# bootloader.net
KiCad netlist of a schematic drawn in EAGLE
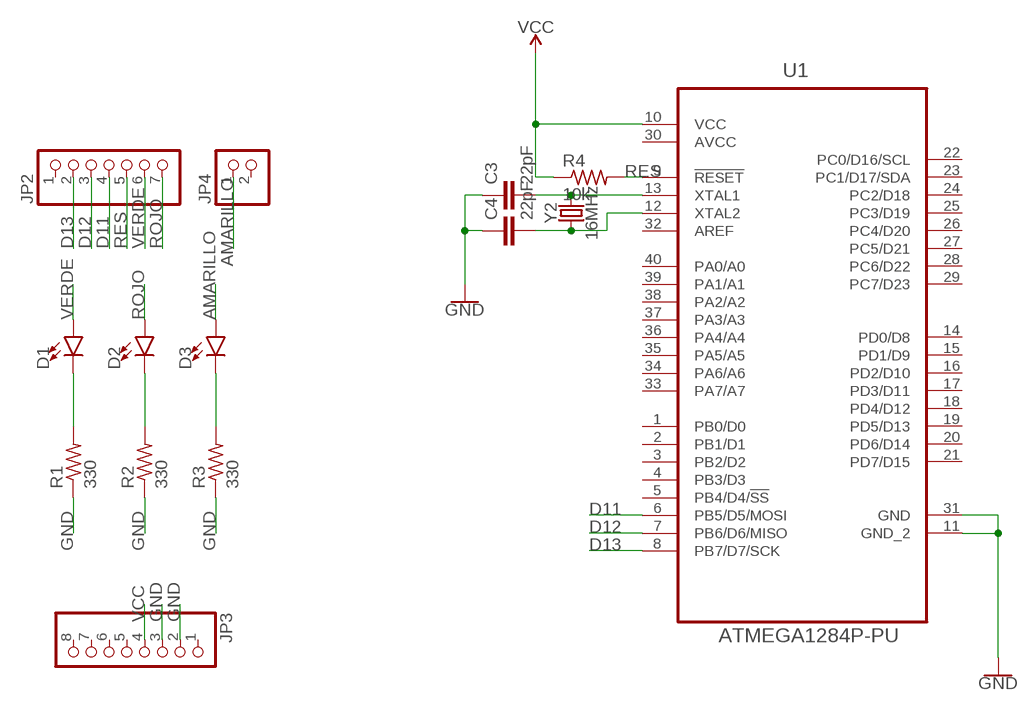
[diagram p0: schematic, sheet 1]

(export (version "E")
  (design (tool "Eeschema 10.0.6"))
  (components
    (comp (ref "C3")
      (value "22pF")
      (footprint "eagle-import:C1206")
      (libsource (lib "eagle-import") (part "C-EUC1206"))
    )
    (comp (ref "C4")
      (value "22pF")
      (footprint "eagle-import:C1206")
      (libsource (lib "eagle-import") (part "C-EUC1206"))
    )
    (comp (ref "D1")
      (value "LED1206")
      (footprint "eagle-import:LED-1206")
      (libsource (lib "eagle-import") (part "LED1206"))
    )
    (comp (ref "D2")
      (value "LED1206")
      (footprint "eagle-import:LED-1206")
      (libsource (lib "eagle-import") (part "LED1206"))
    )
    (comp (ref "D3")
      (value "LED1206")
      (footprint "eagle-import:LED-1206")
      (libsource (lib "eagle-import") (part "LED1206"))
    )
    (comp (ref "JP2")
      (value "PINHD-1X7")
      (footprint "eagle-import:1X07")
      (libsource (lib "eagle-import") (part "PINHD-1X7"))
    )
    (comp (ref "JP3")
      (value "PINHD-1X8")
      (footprint "eagle-import:1X08")
      (libsource (lib "eagle-import") (part "PINHD-1X8"))
    )
    (comp (ref "JP4")
      (value "PINHD-1X2")
      (footprint "eagle-import:1X02")
      (libsource (lib "eagle-import") (part "PINHD-1X2"))
    )
    (comp (ref "R1")
      (value "330")
      (footprint "eagle-import:R1206")
      (libsource (lib "eagle-import") (part "R-US_R1206"))
    )
    (comp (ref "R2")
      (value "330")
      (footprint "eagle-import:R1206")
      (libsource (lib "eagle-import") (part "R-US_R1206"))
    )
    (comp (ref "R3")
      (value "330")
      (footprint "eagle-import:R1206")
      (libsource (lib "eagle-import") (part "R-US_R1206"))
    )
    (comp (ref "R4")
      (value "10k")
      (footprint "eagle-import:R1206")
      (libsource (lib "eagle-import") (part "rcl_R-US_R1206"))
    )
    (comp (ref "U1")
      (value "ATMEGA1284P-PU")
      (footprint "eagle-import:DIP254P1524X483-40")
      (fields (field (name "MF") "Microchip"))
      (libsource (lib "eagle-import") (part "ATMEGA1284P-PU"))
    )
    (comp (ref "Y2")
      (value "16MHz")
      (footprint "eagle-import:CRYSTAL-SMD-5X3.2-4PAD")
      (libsource (lib "eagle-import") (part "CRYSTALSMD-5X3.2-4PAD"))
    )
  )
  (nets
    (net (code "1") (name "/AMARILLO") (class "Default")
      (node (ref "D3") (pin "A") (pinfunction "A_A") (pintype "passive"))
      (node (ref "JP4") (pin "1") (pinfunction "1_1") (pintype "passive"))
    )
    (net (code "2") (name "/AVCC") (class "Default")
      (node (ref "U1") (pin "30") (pinfunction "AVCC_30") (pintype "power_in"))
    )
    (net (code "3") (name "/D11") (class "Default")
      (node (ref "JP2") (pin "4") (pinfunction "4_4") (pintype "passive"))
      (node (ref "U1") (pin "6") (pinfunction "PB5/D5/MOSI_6") (pintype "bidirectional"))
    )
    (net (code "4") (name "/D12") (class "Default")
      (node (ref "JP2") (pin "3") (pinfunction "3_3") (pintype "passive"))
      (node (ref "U1") (pin "7") (pinfunction "PB6/D6/MISO_7") (pintype "bidirectional"))
    )
    (net (code "5") (name "/D13") (class "Default")
      (node (ref "JP2") (pin "2") (pinfunction "2_2") (pintype "passive"))
      (node (ref "U1") (pin "8") (pinfunction "PB7/D7/SCK_8") (pintype "bidirectional"))
    )
    (net (code "6") (name "/RES") (class "Default")
      (node (ref "JP2") (pin "5") (pinfunction "5_5") (pintype "passive"))
      (node (ref "R4") (pin "2") (pinfunction "2_2") (pintype "passive"))
      (node (ref "U1") (pin "9") (pinfunction "~{RESET}_9") (pintype "input"))
    )
    (net (code "7") (name "/ROJO") (class "Default")
      (node (ref "D2") (pin "A") (pinfunction "A_A") (pintype "passive"))
      (node (ref "JP2") (pin "7") (pinfunction "7_7") (pintype "passive"))
    )
    (net (code "8") (name "/VERDE") (class "Default")
      (node (ref "D1") (pin "A") (pinfunction "A_A") (pintype "passive"))
      (node (ref "JP2") (pin "6") (pinfunction "6_6") (pintype "passive"))
    )
    (net (code "9") (name "GND") (class "Default")
      (node (ref "C3") (pin "1") (pinfunction "1_1") (pintype "passive"))
      (node (ref "C4") (pin "1") (pinfunction "1_1") (pintype "passive"))
      (node (ref "JP3") (pin "2") (pinfunction "2_2") (pintype "passive"))
      (node (ref "JP3") (pin "3") (pinfunction "3_3") (pintype "passive"))
      (node (ref "R1") (pin "1") (pinfunction "1_1") (pintype "passive"))
      (node (ref "R2") (pin "1") (pinfunction "1_1") (pintype "passive"))
      (node (ref "R3") (pin "1") (pinfunction "1_1") (pintype "passive"))
      (node (ref "U1") (pin "11") (pinfunction "GND_2_11") (pintype "passive"))
      (node (ref "U1") (pin "31") (pinfunction "GND_31") (pintype "passive"))
    )
    (net (code "10") (name "Net-(D1-PadC)") (class "Default")
      (node (ref "D1") (pin "C") (pinfunction "C_C") (pintype "passive"))
      (node (ref "R1") (pin "2") (pinfunction "2_2") (pintype "passive"))
    )
    (net (code "11") (name "Net-(D2-PadC)") (class "Default")
      (node (ref "D2") (pin "C") (pinfunction "C_C") (pintype "passive"))
      (node (ref "R2") (pin "2") (pinfunction "2_2") (pintype "passive"))
    )
    (net (code "12") (name "Net-(D3-PadC)") (class "Default")
      (node (ref "D3") (pin "C") (pinfunction "C_C") (pintype "passive"))
      (node (ref "R3") (pin "2") (pinfunction "2_2") (pintype "passive"))
    )
    (net (code "13") (name "Net-(U1-XTAL1)") (class "Default")
      (node (ref "C3") (pin "2") (pinfunction "2_2") (pintype "passive"))
      (node (ref "U1") (pin "13") (pinfunction "XTAL1_13") (pintype "input"))
      (node (ref "Y2") (pin "3") (pinfunction "2_3") (pintype "passive"))
    )
    (net (code "14") (name "Net-(U1-XTAL2)") (class "Default")
      (node (ref "C4") (pin "2") (pinfunction "2_2") (pintype "passive"))
      (node (ref "U1") (pin "12") (pinfunction "XTAL2_12") (pintype "output"))
      (node (ref "Y2") (pin "1") (pinfunction "1_1") (pintype "passive"))
    )
    (net (code "15") (name "VCC") (class "Default")
      (node (ref "JP3") (pin "4") (pinfunction "4_4") (pintype "passive"))
      (node (ref "R4") (pin "1") (pinfunction "1_1") (pintype "passive"))
      (node (ref "U1") (pin "10") (pinfunction "VCC_10") (pintype "power_in"))
    )
    (net (code "16") (name "unconnected-(JP2-Pad1)") (class "Default")
      (node (ref "JP2") (pin "1") (pinfunction "1_1") (pintype "passive"))
    )
    (net (code "17") (name "unconnected-(JP3-Pad1)") (class "Default")
      (node (ref "JP3") (pin "1") (pinfunction "1_1") (pintype "passive"))
    )
    (net (code "18") (name "unconnected-(JP3-Pad5)") (class "Default")
      (node (ref "JP3") (pin "5") (pinfunction "5_5") (pintype "passive"))
    )
    (net (code "19") (name "unconnected-(JP3-Pad6)") (class "Default")
      (node (ref "JP3") (pin "6") (pinfunction "6_6") (pintype "passive"))
    )
    (net (code "20") (name "unconnected-(JP3-Pad7)") (class "Default")
      (node (ref "JP3") (pin "7") (pinfunction "7_7") (pintype "passive"))
    )
    (net (code "21") (name "unconnected-(JP3-Pad8)") (class "Default")
      (node (ref "JP3") (pin "8") (pinfunction "8_8") (pintype "passive"))
    )
    (net (code "22") (name "unconnected-(JP4-Pad2)") (class "Default")
      (node (ref "JP4") (pin "2") (pinfunction "2_2") (pintype "passive"))
    )
    (net (code "23") (name "unconnected-(U1-AREF-Pad32)") (class "Default")
      (node (ref "U1") (pin "32") (pinfunction "AREF_32") (pintype "input"))
    )
    (net (code "24") (name "unconnected-(U1-PA0{slash}A0-Pad40)") (class "Default")
      (node (ref "U1") (pin "40") (pinfunction "PA0/A0_40") (pintype "bidirectional"))
    )
    (net (code "25") (name "unconnected-(U1-PA1{slash}A1-Pad39)") (class "Default")
      (node (ref "U1") (pin "39") (pinfunction "PA1/A1_39") (pintype "bidirectional"))
    )
    (net (code "26") (name "unconnected-(U1-PA2{slash}A2-Pad38)") (class "Default")
      (node (ref "U1") (pin "38") (pinfunction "PA2/A2_38") (pintype "bidirectional"))
    )
    (net (code "27") (name "unconnected-(U1-PA3{slash}A3-Pad37)") (class "Default")
      (node (ref "U1") (pin "37") (pinfunction "PA3/A3_37") (pintype "bidirectional"))
    )
    (net (code "28") (name "unconnected-(U1-PA4{slash}A4-Pad36)") (class "Default")
      (node (ref "U1") (pin "36") (pinfunction "PA4/A4_36") (pintype "bidirectional"))
    )
    (net (code "29") (name "unconnected-(U1-PA5{slash}A5-Pad35)") (class "Default")
      (node (ref "U1") (pin "35") (pinfunction "PA5/A5_35") (pintype "bidirectional"))
    )
    (net (code "30") (name "unconnected-(U1-PA6{slash}A6-Pad34)") (class "Default")
      (node (ref "U1") (pin "34") (pinfunction "PA6/A6_34") (pintype "bidirectional"))
    )
    (net (code "31") (name "unconnected-(U1-PA7{slash}A7-Pad33)") (class "Default")
      (node (ref "U1") (pin "33") (pinfunction "PA7/A7_33") (pintype "bidirectional"))
    )
    (net (code "32") (name "unconnected-(U1-PB0{slash}D0-Pad1)") (class "Default")
      (node (ref "U1") (pin "1") (pinfunction "PB0/D0_1") (pintype "bidirectional"))
    )
    (net (code "33") (name "unconnected-(U1-PB1{slash}D1-Pad2)") (class "Default")
      (node (ref "U1") (pin "2") (pinfunction "PB1/D1_2") (pintype "bidirectional"))
    )
    (net (code "34") (name "unconnected-(U1-PB2{slash}D2-Pad3)") (class "Default")
      (node (ref "U1") (pin "3") (pinfunction "PB2/D2_3") (pintype "bidirectional"))
    )
    (net (code "35") (name "unconnected-(U1-PB3{slash}D3-Pad4)") (class "Default")
      (node (ref "U1") (pin "4") (pinfunction "PB3/D3_4") (pintype "bidirectional"))
    )
    (net (code "36") (name "unconnected-(U1-PB4{slash}D4{slash}~{SS}-Pad5)") (class "Default")
      (node (ref "U1") (pin "5") (pinfunction "PB4/D4/~{SS}_5") (pintype "bidirectional"))
    )
    (net (code "37") (name "unconnected-(U1-PC0{slash}D16{slash}SCL-Pad22)") (class "Default")
      (node (ref "U1") (pin "22") (pinfunction "PC0/D16/SCL_22") (pintype "bidirectional"))
    )
    (net (code "38") (name "unconnected-(U1-PC1{slash}D17{slash}SDA-Pad23)") (class "Default")
      (node (ref "U1") (pin "23") (pinfunction "PC1/D17/SDA_23") (pintype "bidirectional"))
    )
    (net (code "39") (name "unconnected-(U1-PC2{slash}D18-Pad24)") (class "Default")
      (node (ref "U1") (pin "24") (pinfunction "PC2/D18_24") (pintype "bidirectional"))
    )
    (net (code "40") (name "unconnected-(U1-PC3{slash}D19-Pad25)") (class "Default")
      (node (ref "U1") (pin "25") (pinfunction "PC3/D19_25") (pintype "bidirectional"))
    )
    (net (code "41") (name "unconnected-(U1-PC4{slash}D20-Pad26)") (class "Default")
      (node (ref "U1") (pin "26") (pinfunction "PC4/D20_26") (pintype "bidirectional"))
    )
    (net (code "42") (name "unconnected-(U1-PC5{slash}D21-Pad27)") (class "Default")
      (node (ref "U1") (pin "27") (pinfunction "PC5/D21_27") (pintype "bidirectional"))
    )
    (net (code "43") (name "unconnected-(U1-PC6{slash}D22-Pad28)") (class "Default")
      (node (ref "U1") (pin "28") (pinfunction "PC6/D22_28") (pintype "bidirectional"))
    )
    (net (code "44") (name "unconnected-(U1-PC7{slash}D23-Pad29)") (class "Default")
      (node (ref "U1") (pin "29") (pinfunction "PC7/D23_29") (pintype "bidirectional"))
    )
    (net (code "45") (name "unconnected-(U1-PD0{slash}D8-Pad14)") (class "Default")
      (node (ref "U1") (pin "14") (pinfunction "PD0/D8_14") (pintype "bidirectional"))
    )
    (net (code "46") (name "unconnected-(U1-PD1{slash}D9-Pad15)") (class "Default")
      (node (ref "U1") (pin "15") (pinfunction "PD1/D9_15") (pintype "bidirectional"))
    )
    (net (code "47") (name "unconnected-(U1-PD2{slash}D10-Pad16)") (class "Default")
      (node (ref "U1") (pin "16") (pinfunction "PD2/D10_16") (pintype "bidirectional"))
    )
    (net (code "48") (name "unconnected-(U1-PD3{slash}D11-Pad17)") (class "Default")
      (node (ref "U1") (pin "17") (pinfunction "PD3/D11_17") (pintype "bidirectional"))
    )
    (net (code "49") (name "unconnected-(U1-PD4{slash}D12-Pad18)") (class "Default")
      (node (ref "U1") (pin "18") (pinfunction "PD4/D12_18") (pintype "bidirectional"))
    )
    (net (code "50") (name "unconnected-(U1-PD5{slash}D13-Pad19)") (class "Default")
      (node (ref "U1") (pin "19") (pinfunction "PD5/D13_19") (pintype "bidirectional"))
    )
    (net (code "51") (name "unconnected-(U1-PD6{slash}D14-Pad20)") (class "Default")
      (node (ref "U1") (pin "20") (pinfunction "PD6/D14_20") (pintype "bidirectional"))
    )
    (net (code "52") (name "unconnected-(U1-PD7{slash}D15-Pad21)") (class "Default")
      (node (ref "U1") (pin "21") (pinfunction "PD7/D15_21") (pintype "bidirectional"))
    )
  )
)
